# ItsyBitsy_Expander_v1_0.net
KiCad netlist of a schematic drawn in EAGLE
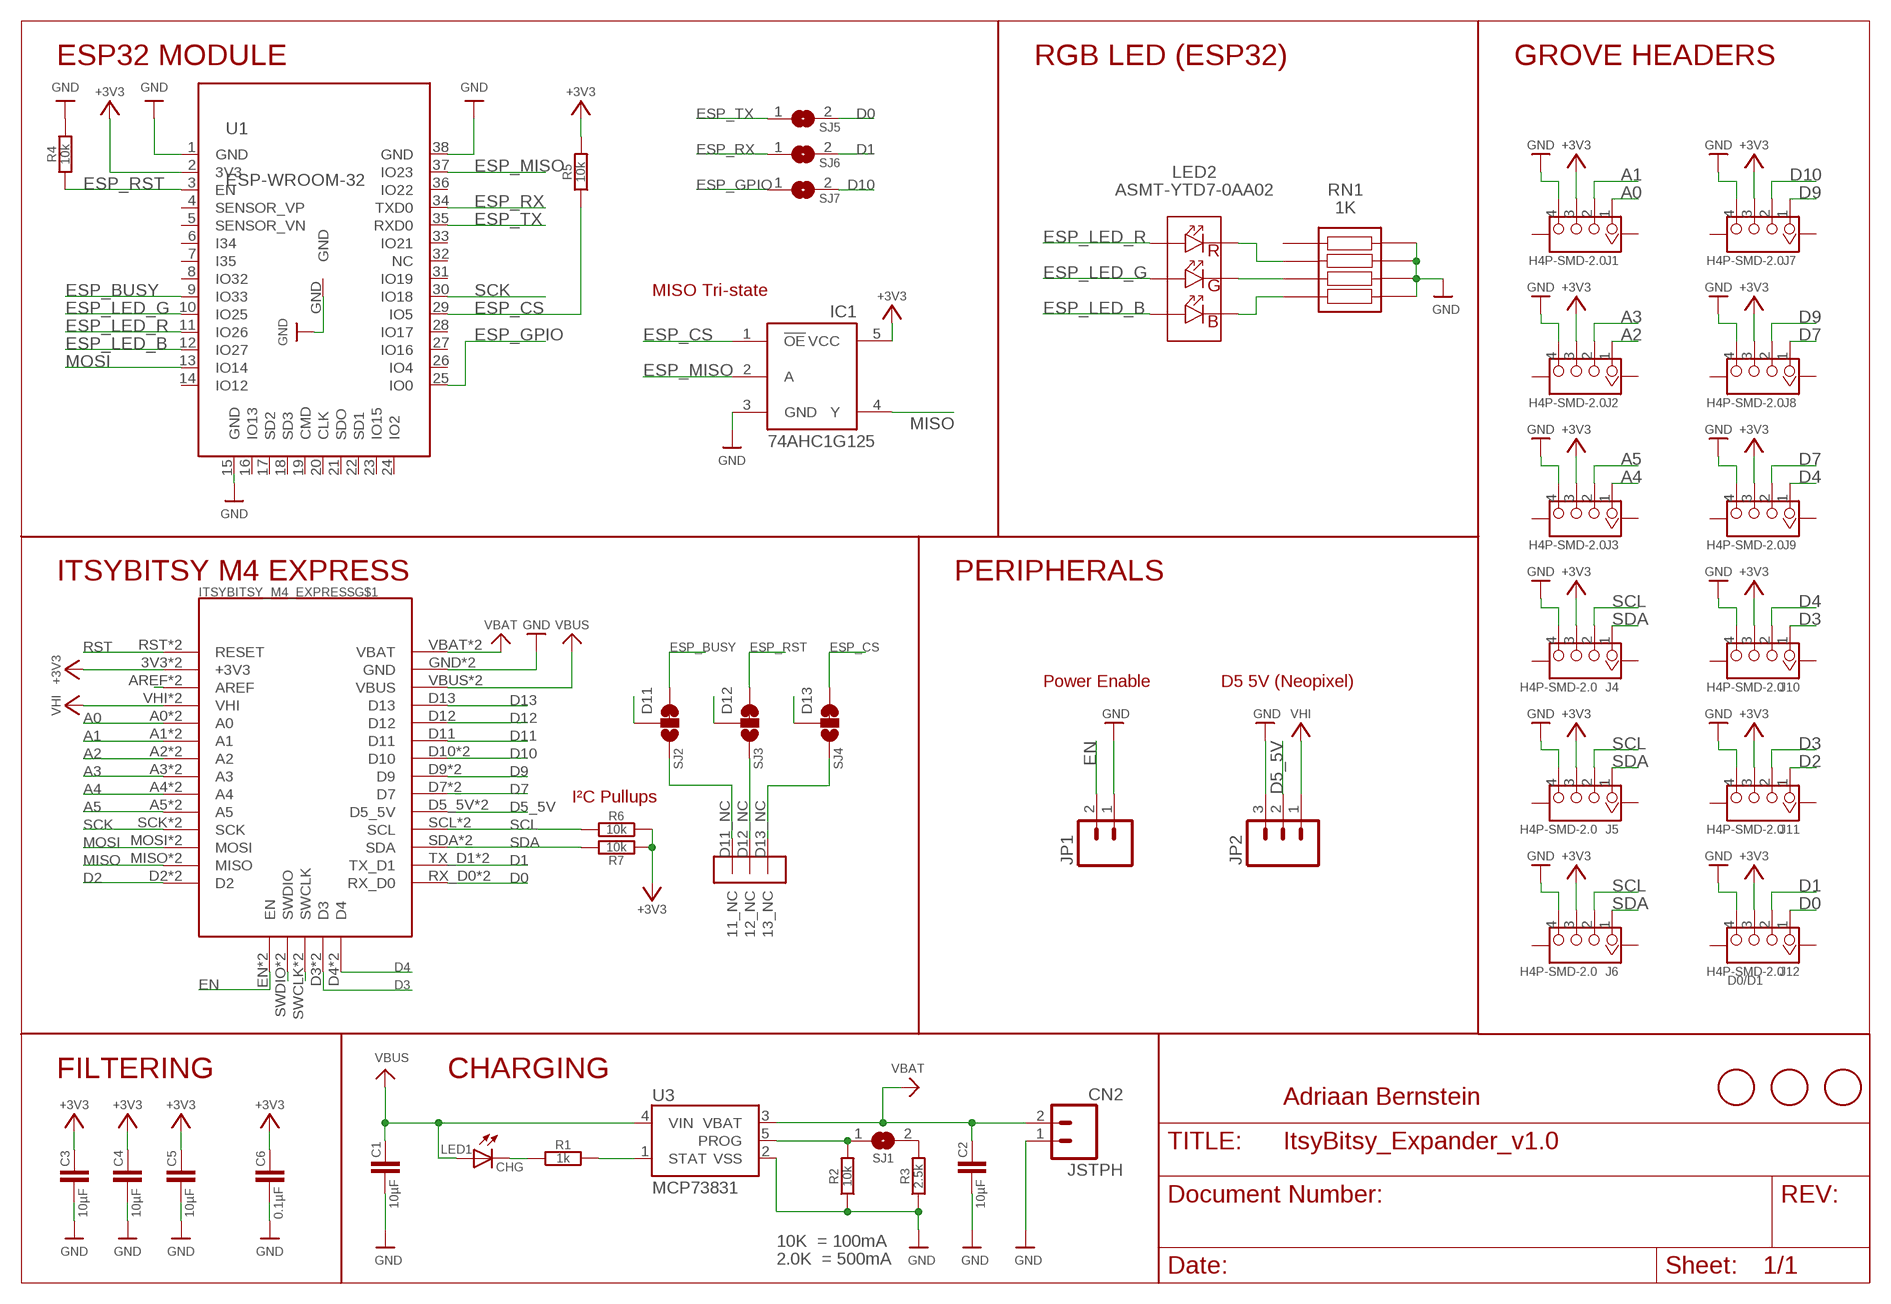
[diagram p0: schematic, sheet 1]

(export (version "E")
  (design (tool "Eeschema 10.0.6"))
  (components
    (comp (ref "C1")
      (value "10µF")
      (footprint "eagle-import:C0805")
      (libsource (lib "eagle-import") (part "C-EUC0805"))
    )
    (comp (ref "C2")
      (value "10µF")
      (footprint "eagle-import:C0805")
      (libsource (lib "eagle-import") (part "C-EUC0805"))
    )
    (comp (ref "C3")
      (value "10µF")
      (footprint "eagle-import:C0805")
      (libsource (lib "eagle-import") (part "C-EUC0805"))
    )
    (comp (ref "C4")
      (value "10µF")
      (footprint "eagle-import:C0805")
      (libsource (lib "eagle-import") (part "C-EUC0805"))
    )
    (comp (ref "C5")
      (value "10µF")
      (footprint "eagle-import:C0805")
      (libsource (lib "eagle-import") (part "C-EUC0805"))
    )
    (comp (ref "C6")
      (value "0.1µF")
      (footprint "eagle-import:C0603")
      (libsource (lib "eagle-import") (part "C-EUC0603"))
    )
    (comp (ref "CN2")
      (value "JSTPH")
      (footprint "eagle-import:JST-2-SMD")
      (libsource (lib "eagle-import") (part "M02-JST-2MM-SMT"))
    )
    (comp (ref "IC1")
      (value "74AHC1G125")
      (footprint "eagle-import:SOT23-5L")
      (libsource (lib "eagle-import") (part "74AHC1G125"))
    )
    (comp (ref "ITSYBITSY_M4_EXPRESS")
      (value "ITSYBITSY_M4_NC")
      (footprint "eagle-import:ITSYBITSY_M4_MIXED_DOUBLEHEADERS_ALL_NC")
      (libsource (lib "eagle-import") (part "ITSYBITSY_M4_NC"))
    )
    (comp (ref "J1")
      (value "H4P-SMD-2.0")
      (footprint "eagle-import:HW4-SMD-2.0")
      (libsource (lib "eagle-import") (part "GROVE-CONNECTOR-SMD(4+2P-2.0)"))
    )
    (comp (ref "J2")
      (value "H4P-SMD-2.0")
      (footprint "eagle-import:HW4-SMD-2.0")
      (libsource (lib "eagle-import") (part "GROVE-CONNECTOR-SMD(4+2P-2.0)"))
    )
    (comp (ref "J3")
      (value "H4P-SMD-2.0")
      (footprint "eagle-import:HW4-SMD-2.0")
      (libsource (lib "eagle-import") (part "GROVE-CONNECTOR-SMD(4+2P-2.0)"))
    )
    (comp (ref "J4")
      (value "H4P-SMD-2.0")
      (footprint "eagle-import:HW4-SMD-2.0")
      (libsource (lib "eagle-import") (part "GROVE-CONNECTOR-SMD(4+2P-2.0)"))
    )
    (comp (ref "J5")
      (value "H4P-SMD-2.0")
      (footprint "eagle-import:HW4-SMD-2.0")
      (libsource (lib "eagle-import") (part "GROVE-CONNECTOR-SMD(4+2P-2.0)"))
    )
    (comp (ref "J6")
      (value "H4P-SMD-2.0")
      (footprint "eagle-import:HW4-SMD-2.0")
      (libsource (lib "eagle-import") (part "GROVE-CONNECTOR-SMD(4+2P-2.0)"))
    )
    (comp (ref "J7")
      (value "H4P-SMD-2.0")
      (footprint "eagle-import:HW4-SMD-2.0")
      (libsource (lib "eagle-import") (part "GROVE-CONNECTOR-SMD(4+2P-2.0)"))
    )
    (comp (ref "J8")
      (value "H4P-SMD-2.0")
      (footprint "eagle-import:HW4-SMD-2.0")
      (libsource (lib "eagle-import") (part "GROVE-CONNECTOR-SMD(4+2P-2.0)"))
    )
    (comp (ref "J9")
      (value "H4P-SMD-2.0")
      (footprint "eagle-import:HW4-SMD-2.0")
      (libsource (lib "eagle-import") (part "GROVE-CONNECTOR-SMD(4+2P-2.0)"))
    )
    (comp (ref "J10")
      (value "H4P-SMD-2.0")
      (footprint "eagle-import:HW4-SMD-2.0")
      (libsource (lib "eagle-import") (part "GROVE-CONNECTOR-SMD(4+2P-2.0)"))
    )
    (comp (ref "J11")
      (value "H4P-SMD-2.0")
      (footprint "eagle-import:HW4-SMD-2.0")
      (libsource (lib "eagle-import") (part "GROVE-CONNECTOR-SMD(4+2P-2.0)"))
    )
    (comp (ref "J12")
      (value "H4P-SMD-2.0")
      (footprint "eagle-import:HW4-SMD-2.0")
      (libsource (lib "eagle-import") (part "GROVE-CONNECTOR-SMD(4+2P-2.0)"))
    )
    (comp (ref "JP1")
      (value "M02PTH")
      (footprint "eagle-import:1X02")
      (libsource (lib "eagle-import") (part "M02PTH"))
    )
    (comp (ref "JP2")
      (value "M03PTH")
      (footprint "eagle-import:1X03")
      (libsource (lib "eagle-import") (part "M03PTH"))
    )
    (comp (ref "LED1")
      (value "CHG")
      (footprint "eagle-import:CHIP-LED0603")
      (libsource (lib "eagle-import") (part "LEDCHIP-LED0603"))
    )
    (comp (ref "LED2")
      (value "ASMT-YTD7-0AA02")
      (footprint "eagle-import:ASMTYTD70AA02")
      (fields (field (name "MOUSER_PART_NUMBER") "630-ASMT-YTD7-0AA02"))
      (libsource (lib "eagle-import") (part "ASMT-YTD7-0AA02"))
    )
    (comp (ref "R1")
      (value "1k")
      (footprint "eagle-import:R0603")
      (libsource (lib "eagle-import") (part "R-EU_R0603"))
    )
    (comp (ref "R2")
      (value "10k")
      (footprint "eagle-import:R0603")
      (libsource (lib "eagle-import") (part "R-EU_R0603"))
    )
    (comp (ref "R3")
      (value "2.5k")
      (footprint "eagle-import:R0603")
      (libsource (lib "eagle-import") (part "R-EU_R0603"))
    )
    (comp (ref "R4")
      (value "10k")
      (footprint "eagle-import:R0603")
      (libsource (lib "eagle-import") (part "R-EU_R0603"))
    )
    (comp (ref "R5")
      (value "10k")
      (footprint "eagle-import:R0603")
      (libsource (lib "eagle-import") (part "R-EU_R0603"))
    )
    (comp (ref "R6")
      (value "10k")
      (footprint "eagle-import:R0603")
      (libsource (lib "eagle-import") (part "R-EU_R0603"))
    )
    (comp (ref "R7")
      (value "10k")
      (footprint "eagle-import:R0603")
      (libsource (lib "eagle-import") (part "R-EU_R0603"))
    )
    (comp (ref "RN1")
      (value "1K")
      (footprint "eagle-import:CAY1647R0F4LF")
      (fields
        (field (name "MANUFACTURER_PART_NUMBER") "CAY16-221J4AS")
        (field (name "MOUSER_PART_NUMBER") "652-CAY16-221J4AS")
      )
      (libsource (lib "eagle-import") (part "CAY16-221J4AS"))
    )
    (comp (ref "SJ1") (value "SJ") (footprint "eagle-import:SJ") (libsource (lib "eagle-import") (part "SJ")))
    (comp (ref "SJ5") (value "SJ") (footprint "eagle-import:SJ") (libsource (lib "eagle-import") (part "SJ")))
    (comp (ref "SJ6") (value "SJ") (footprint "eagle-import:SJ") (libsource (lib "eagle-import") (part "SJ")))
    (comp (ref "SJ7") (value "SJ") (footprint "eagle-import:SJ") (libsource (lib "eagle-import") (part "SJ")))
    (comp (ref "SJ_D11")
      (value "SJ2")
      (footprint "eagle-import:SJ_2WAY_CLOSED")
      (libsource (lib "eagle-import") (part "SJ_2WAY_CLOSED"))
    )
    (comp (ref "SJ_D12")
      (value "SJ3")
      (footprint "eagle-import:SJ_2WAY_CLOSED")
      (libsource (lib "eagle-import") (part "SJ_2WAY_CLOSED"))
    )
    (comp (ref "SJ_D13")
      (value "SJ4")
      (footprint "eagle-import:SJ_2WAY_CLOSED")
      (libsource (lib "eagle-import") (part "SJ_2WAY_CLOSED"))
    )
    (comp (ref "U$23")
      (value "FIDUCIAL")
      (footprint "eagle-import:FIDUCIAL_1MM")
      (libsource (lib "eagle-import") (part "FIDUCIAL"))
    )
    (comp (ref "U$35")
      (value "FIDUCIAL")
      (footprint "eagle-import:FIDUCIAL_1MM")
      (libsource (lib "eagle-import") (part "FIDUCIAL"))
    )
    (comp (ref "U$36")
      (value "FIDUCIAL")
      (footprint "eagle-import:FIDUCIAL_1MM")
      (libsource (lib "eagle-import") (part "FIDUCIAL"))
    )
    (comp (ref "U1")
      (value "ESP-WROOM-32")
      (footprint "eagle-import:ESP-WROOM-32")
      (libsource (lib "eagle-import") (part "ESP-WROOM-32"))
    )
    (comp (ref "U3")
      (value "MCP73831")
      (footprint "eagle-import:SOT23-5")
      (libsource (lib "eagle-import") (part "MCP73831"))
    )
  )
  (nets
    (net (code "1") (name "+3V3") (class "Default")
      (node (ref "C3") (pin "1") (pinfunction "1_1") (pintype "passive"))
      (node (ref "C4") (pin "1") (pinfunction "1_1") (pintype "passive"))
      (node (ref "C5") (pin "1") (pinfunction "1_1") (pintype "passive"))
      (node (ref "C6") (pin "1") (pinfunction "1_1") (pintype "passive"))
      (node (ref "IC1") (pin "5") (pinfunction "VCC_5") (pintype "power_in"))
      (node (ref "ITSYBITSY_M4_EXPRESS") (pin "3V3") (pinfunction "+3V3_3V3") (pintype "bidirectional"))
      (node (ref "ITSYBITSY_M4_EXPRESS") (pin "3V3_2") (pinfunction "+3V3_3V3_2") (pintype "bidirectional"))
      (node (ref "J1") (pin "3") (pinfunction "3_3") (pintype "bidirectional"))
      (node (ref "J10") (pin "3") (pinfunction "3_3") (pintype "bidirectional"))
      (node (ref "J11") (pin "3") (pinfunction "3_3") (pintype "bidirectional"))
      (node (ref "J12") (pin "3") (pinfunction "3_3") (pintype "bidirectional"))
      (node (ref "J2") (pin "3") (pinfunction "3_3") (pintype "bidirectional"))
      (node (ref "J3") (pin "3") (pinfunction "3_3") (pintype "bidirectional"))
      (node (ref "J4") (pin "3") (pinfunction "3_3") (pintype "bidirectional"))
      (node (ref "J5") (pin "3") (pinfunction "3_3") (pintype "bidirectional"))
      (node (ref "J6") (pin "3") (pinfunction "3_3") (pintype "bidirectional"))
      (node (ref "J7") (pin "3") (pinfunction "3_3") (pintype "bidirectional"))
      (node (ref "J8") (pin "3") (pinfunction "3_3") (pintype "bidirectional"))
      (node (ref "J9") (pin "3") (pinfunction "3_3") (pintype "bidirectional"))
      (node (ref "R5") (pin "2") (pinfunction "2_2") (pintype "passive"))
      (node (ref "R6") (pin "1") (pinfunction "1_1") (pintype "passive"))
      (node (ref "R7") (pin "1") (pinfunction "1_1") (pintype "passive"))
      (node (ref "U1") (pin "2") (pinfunction "3V3_2") (pintype "bidirectional"))
    )
    (net (code "2") (name "/A0") (class "Default")
      (node (ref "ITSYBITSY_M4_EXPRESS") (pin "A0") (pinfunction "A0_A0") (pintype "bidirectional"))
      (node (ref "ITSYBITSY_M4_EXPRESS") (pin "A0_2") (pinfunction "A0_A0_2") (pintype "bidirectional"))
      (node (ref "J1") (pin "1") (pinfunction "1_1") (pintype "bidirectional"))
    )
    (net (code "3") (name "/A1") (class "Default")
      (node (ref "ITSYBITSY_M4_EXPRESS") (pin "A1") (pinfunction "A1_A1") (pintype "bidirectional"))
      (node (ref "ITSYBITSY_M4_EXPRESS") (pin "A1_2") (pinfunction "A1_A1_2") (pintype "bidirectional"))
      (node (ref "J1") (pin "2") (pinfunction "2_2") (pintype "bidirectional"))
    )
    (net (code "4") (name "/A2") (class "Default")
      (node (ref "ITSYBITSY_M4_EXPRESS") (pin "A2") (pinfunction "A2_A2") (pintype "bidirectional"))
      (node (ref "ITSYBITSY_M4_EXPRESS") (pin "A2_2") (pinfunction "A2_A2_2") (pintype "bidirectional"))
      (node (ref "J2") (pin "1") (pinfunction "1_1") (pintype "bidirectional"))
    )
    (net (code "5") (name "/A3") (class "Default")
      (node (ref "ITSYBITSY_M4_EXPRESS") (pin "A3") (pinfunction "A3_A3") (pintype "bidirectional"))
      (node (ref "ITSYBITSY_M4_EXPRESS") (pin "A3_3") (pinfunction "A3_A3_3") (pintype "bidirectional"))
      (node (ref "J2") (pin "2") (pinfunction "2_2") (pintype "bidirectional"))
    )
    (net (code "6") (name "/A4") (class "Default")
      (node (ref "ITSYBITSY_M4_EXPRESS") (pin "A4") (pinfunction "A4_A4") (pintype "bidirectional"))
      (node (ref "ITSYBITSY_M4_EXPRESS") (pin "A4_2") (pinfunction "A4_A4_2") (pintype "bidirectional"))
      (node (ref "J3") (pin "1") (pinfunction "1_1") (pintype "bidirectional"))
    )
    (net (code "7") (name "/A5") (class "Default")
      (node (ref "ITSYBITSY_M4_EXPRESS") (pin "A5") (pinfunction "A5_A5") (pintype "bidirectional"))
      (node (ref "ITSYBITSY_M4_EXPRESS") (pin "A5_2") (pinfunction "A5_A5_2") (pintype "bidirectional"))
      (node (ref "J3") (pin "2") (pinfunction "2_2") (pintype "bidirectional"))
    )
    (net (code "8") (name "/D0") (class "Default")
      (node (ref "ITSYBITSY_M4_EXPRESS") (pin "RX_D0") (pinfunction "RX_D0_RX_D0") (pintype "bidirectional"))
      (node (ref "ITSYBITSY_M4_EXPRESS") (pin "RX_D0_2") (pinfunction "RX_D0_RX_D0_2") (pintype "bidirectional"))
      (node (ref "J12") (pin "1") (pinfunction "1_1") (pintype "bidirectional"))
      (node (ref "SJ5") (pin "2") (pinfunction "2_2") (pintype "passive"))
    )
    (net (code "9") (name "/D1") (class "Default")
      (node (ref "ITSYBITSY_M4_EXPRESS") (pin "TX_D1") (pinfunction "TX_D1_TX_D1") (pintype "bidirectional"))
      (node (ref "ITSYBITSY_M4_EXPRESS") (pin "TX_D1_2") (pinfunction "TX_D1_TX_D1_2") (pintype "bidirectional"))
      (node (ref "J12") (pin "2") (pinfunction "2_2") (pintype "bidirectional"))
      (node (ref "SJ6") (pin "2") (pinfunction "2_2") (pintype "passive"))
    )
    (net (code "10") (name "/D2") (class "Default")
      (node (ref "ITSYBITSY_M4_EXPRESS") (pin "D2") (pinfunction "D2_D2") (pintype "bidirectional"))
      (node (ref "ITSYBITSY_M4_EXPRESS") (pin "D2_2") (pinfunction "D2_D2_2") (pintype "bidirectional"))
      (node (ref "J11") (pin "1") (pinfunction "1_1") (pintype "bidirectional"))
    )
    (net (code "11") (name "/D3") (class "Default")
      (node (ref "ITSYBITSY_M4_EXPRESS") (pin "D3") (pinfunction "D3_D3") (pintype "bidirectional"))
      (node (ref "ITSYBITSY_M4_EXPRESS") (pin "D3_2") (pinfunction "D3_D3_2") (pintype "bidirectional"))
      (node (ref "J10") (pin "1") (pinfunction "1_1") (pintype "bidirectional"))
      (node (ref "J11") (pin "2") (pinfunction "2_2") (pintype "bidirectional"))
    )
    (net (code "12") (name "/D4") (class "Default")
      (node (ref "ITSYBITSY_M4_EXPRESS") (pin "D4") (pinfunction "D4_D4") (pintype "bidirectional"))
      (node (ref "ITSYBITSY_M4_EXPRESS") (pin "D4_2") (pinfunction "D4_D4_2") (pintype "bidirectional"))
      (node (ref "J10") (pin "2") (pinfunction "2_2") (pintype "bidirectional"))
      (node (ref "J9") (pin "1") (pinfunction "1_1") (pintype "bidirectional"))
    )
    (net (code "13") (name "/D5_5V") (class "Default")
      (node (ref "ITSYBITSY_M4_EXPRESS") (pin "D5_5V") (pinfunction "D5_5V_D5_5V") (pintype "bidirectional"))
      (node (ref "ITSYBITSY_M4_EXPRESS") (pin "D5_5V_2") (pinfunction "D5_5V_D5_5V_2") (pintype "bidirectional"))
      (node (ref "JP2") (pin "2") (pinfunction "2_2") (pintype "passive"))
    )
    (net (code "14") (name "/D7") (class "Default")
      (node (ref "ITSYBITSY_M4_EXPRESS") (pin "D7") (pinfunction "D7_D7") (pintype "bidirectional"))
      (node (ref "ITSYBITSY_M4_EXPRESS") (pin "D7_2") (pinfunction "D7_D7_2") (pintype "bidirectional"))
      (node (ref "J8") (pin "1") (pinfunction "1_1") (pintype "bidirectional"))
      (node (ref "J9") (pin "2") (pinfunction "2_2") (pintype "bidirectional"))
    )
    (net (code "15") (name "/D9") (class "Default")
      (node (ref "ITSYBITSY_M4_EXPRESS") (pin "D9") (pinfunction "D9_D9") (pintype "bidirectional"))
      (node (ref "ITSYBITSY_M4_EXPRESS") (pin "D9_2") (pinfunction "D9_D9_2") (pintype "bidirectional"))
      (node (ref "J7") (pin "1") (pinfunction "1_1") (pintype "bidirectional"))
      (node (ref "J8") (pin "2") (pinfunction "2_2") (pintype "bidirectional"))
    )
    (net (code "16") (name "/D10") (class "Default")
      (node (ref "ITSYBITSY_M4_EXPRESS") (pin "D10") (pinfunction "D10_D10") (pintype "bidirectional"))
      (node (ref "ITSYBITSY_M4_EXPRESS") (pin "D10_2") (pinfunction "D10_D10_2") (pintype "bidirectional"))
      (node (ref "J7") (pin "2") (pinfunction "2_2") (pintype "bidirectional"))
      (node (ref "SJ7") (pin "2") (pinfunction "2_2") (pintype "passive"))
    )
    (net (code "17") (name "/D11") (class "Default")
      (node (ref "ITSYBITSY_M4_EXPRESS") (pin "D11") (pinfunction "D11_D11") (pintype "bidirectional"))
      (node (ref "SJ_D11") (pin "2") (pinfunction "2_2") (pintype "passive"))
    )
    (net (code "18") (name "/D12") (class "Default")
      (node (ref "ITSYBITSY_M4_EXPRESS") (pin "D12") (pinfunction "D12_D12") (pintype "bidirectional"))
      (node (ref "SJ_D12") (pin "2") (pinfunction "2_2") (pintype "passive"))
    )
    (net (code "19") (name "/D13") (class "Default")
      (node (ref "ITSYBITSY_M4_EXPRESS") (pin "D13") (pinfunction "D13_D13") (pintype "bidirectional"))
      (node (ref "SJ_D13") (pin "2") (pinfunction "2_2") (pintype "passive"))
    )
    (net (code "20") (name "/EN") (class "Default")
      (node (ref "ITSYBITSY_M4_EXPRESS") (pin "EN") (pinfunction "EN_EN") (pintype "bidirectional"))
      (node (ref "ITSYBITSY_M4_EXPRESS") (pin "EN_2") (pinfunction "EN_EN_2") (pintype "bidirectional"))
      (node (ref "JP1") (pin "2") (pinfunction "2_2") (pintype "passive"))
    )
    (net (code "21") (name "/ESP_BUSY") (class "Default")
      (node (ref "SJ_D11") (pin "1") (pinfunction "1_1") (pintype "passive"))
      (node (ref "U1") (pin "9") (pinfunction "IO33_9") (pintype "bidirectional"))
    )
    (net (code "22") (name "/ESP_CS") (class "Default")
      (node (ref "IC1") (pin "1") (pinfunction "~{OE}_1") (pintype "input"))
      (node (ref "R5") (pin "1") (pinfunction "1_1") (pintype "passive"))
      (node (ref "SJ_D13") (pin "1") (pinfunction "1_1") (pintype "passive"))
      (node (ref "U1") (pin "29") (pinfunction "IO5_29") (pintype "bidirectional"))
    )
    (net (code "23") (name "/ESP_GPIO") (class "Default")
      (node (ref "SJ7") (pin "1") (pinfunction "1_1") (pintype "passive"))
      (node (ref "U1") (pin "25") (pinfunction "IO0_25") (pintype "bidirectional"))
    )
    (net (code "24") (name "/ESP_LED_B") (class "Default")
      (node (ref "LED2") (pin "6") (pinfunction "A_BLUE_6") (pintype "bidirectional"))
      (node (ref "U1") (pin "12") (pinfunction "IO27_12") (pintype "bidirectional"))
    )
    (net (code "25") (name "/ESP_LED_G") (class "Default")
      (node (ref "LED2") (pin "5") (pinfunction "A_GREEN_5") (pintype "bidirectional"))
      (node (ref "U1") (pin "10") (pinfunction "IO25_10") (pintype "bidirectional"))
    )
    (net (code "26") (name "/ESP_LED_R") (class "Default")
      (node (ref "LED2") (pin "4") (pinfunction "A_RED_4") (pintype "bidirectional"))
      (node (ref "U1") (pin "11") (pinfunction "IO26_11") (pintype "bidirectional"))
    )
    (net (code "27") (name "/ESP_MISO") (class "Default")
      (node (ref "IC1") (pin "2") (pinfunction "A_2") (pintype "input"))
      (node (ref "U1") (pin "37") (pinfunction "IO23_37") (pintype "bidirectional"))
    )
    (net (code "28") (name "/ESP_RST") (class "Default")
      (node (ref "R4") (pin "1") (pinfunction "1_1") (pintype "passive"))
      (node (ref "SJ_D12") (pin "1") (pinfunction "1_1") (pintype "passive"))
      (node (ref "U1") (pin "3") (pinfunction "EN_3") (pintype "bidirectional"))
    )
    (net (code "29") (name "/ESP_RX") (class "Default")
      (node (ref "SJ6") (pin "1") (pinfunction "1_1") (pintype "passive"))
      (node (ref "U1") (pin "34") (pinfunction "TXD0_34") (pintype "bidirectional"))
    )
    (net (code "30") (name "/ESP_TX") (class "Default")
      (node (ref "SJ5") (pin "1") (pinfunction "1_1") (pintype "passive"))
      (node (ref "U1") (pin "35") (pinfunction "RXD0_35") (pintype "bidirectional"))
    )
    (net (code "31") (name "/MISO") (class "Default")
      (node (ref "IC1") (pin "4") (pinfunction "Y_4") (pintype "output"))
      (node (ref "ITSYBITSY_M4_EXPRESS") (pin "MISO") (pinfunction "MISO_MISO") (pintype "bidirectional"))
      (node (ref "ITSYBITSY_M4_EXPRESS") (pin "MISO_2") (pinfunction "MISO_MISO_2") (pintype "bidirectional"))
    )
    (net (code "32") (name "/MOSI") (class "Default")
      (node (ref "ITSYBITSY_M4_EXPRESS") (pin "MOSI") (pinfunction "MOSI_MOSI") (pintype "bidirectional"))
      (node (ref "ITSYBITSY_M4_EXPRESS") (pin "MOSI_2") (pinfunction "MOSI_MOSI_2") (pintype "bidirectional"))
      (node (ref "U1") (pin "13") (pinfunction "IO14_13") (pintype "bidirectional"))
    )
    (net (code "33") (name "/RST") (class "Default")
      (node (ref "ITSYBITSY_M4_EXPRESS") (pin "RST") (pinfunction "RESET_RST") (pintype "bidirectional"))
      (node (ref "ITSYBITSY_M4_EXPRESS") (pin "RST_2") (pinfunction "RESET_RST_2") (pintype "bidirectional"))
    )
    (net (code "34") (name "/SCK") (class "Default")
      (node (ref "ITSYBITSY_M4_EXPRESS") (pin "SCK") (pinfunction "SCK_SCK") (pintype "bidirectional"))
      (node (ref "ITSYBITSY_M4_EXPRESS") (pin "SCK_2") (pinfunction "SCK_SCK_2") (pintype "bidirectional"))
      (node (ref "U1") (pin "30") (pinfunction "IO18_30") (pintype "bidirectional"))
    )
    (net (code "35") (name "/SCL") (class "Default")
      (node (ref "ITSYBITSY_M4_EXPRESS") (pin "SCL") (pinfunction "SCL_SCL") (pintype "bidirectional"))
      (node (ref "ITSYBITSY_M4_EXPRESS") (pin "SCL_2") (pinfunction "SCL_SCL_2") (pintype "bidirectional"))
      (node (ref "J4") (pin "2") (pinfunction "2_2") (pintype "bidirectional"))
      (node (ref "J5") (pin "2") (pinfunction "2_2") (pintype "bidirectional"))
      (node (ref "J6") (pin "2") (pinfunction "2_2") (pintype "bidirectional"))
      (node (ref "R6") (pin "2") (pinfunction "2_2") (pintype "passive"))
    )
    (net (code "36") (name "/SDA") (class "Default")
      (node (ref "ITSYBITSY_M4_EXPRESS") (pin "SDA") (pinfunction "SDA_SDA") (pintype "bidirectional"))
      (node (ref "ITSYBITSY_M4_EXPRESS") (pin "SDA_2") (pinfunction "SDA_SDA_2") (pintype "bidirectional"))
      (node (ref "J4") (pin "1") (pinfunction "1_1") (pintype "bidirectional"))
      (node (ref "J5") (pin "1") (pinfunction "1_1") (pintype "bidirectional"))
      (node (ref "J6") (pin "1") (pinfunction "1_1") (pintype "bidirectional"))
      (node (ref "R7") (pin "2") (pinfunction "2_2") (pintype "passive"))
    )
    (net (code "37") (name "GND") (class "Default")
      (node (ref "C1") (pin "2") (pinfunction "2_2") (pintype "passive"))
      (node (ref "C2") (pin "2") (pinfunction "2_2") (pintype "passive"))
      (node (ref "C3") (pin "2") (pinfunction "2_2") (pintype "passive"))
      (node (ref "C4") (pin "2") (pinfunction "2_2") (pintype "passive"))
      (node (ref "C5") (pin "2") (pinfunction "2_2") (pintype "passive"))
      (node (ref "C6") (pin "2") (pinfunction "2_2") (pintype "passive"))
      (node (ref "CN2") (pin "1") (pinfunction "1_1") (pintype "passive"))
      (node (ref "IC1") (pin "3") (pinfunction "GND_3") (pintype "power_in"))
      (node (ref "ITSYBITSY_M4_EXPRESS") (pin "GND") (pinfunction "GND_GND") (pintype "bidirectional"))
      (node (ref "ITSYBITSY_M4_EXPRESS") (pin "GND_2") (pinfunction "GND_GND_2") (pintype "bidirectional"))
      (node (ref "J1") (pin "4") (pinfunction "4_4") (pintype "bidirectional"))
      (node (ref "J10") (pin "4") (pinfunction "4_4") (pintype "bidirectional"))
      (node (ref "J11") (pin "4") (pinfunction "4_4") (pintype "bidirectional"))
      (node (ref "J12") (pin "4") (pinfunction "4_4") (pintype "bidirectional"))
      (node (ref "J2") (pin "4") (pinfunction "4_4") (pintype "bidirectional"))
      (node (ref "J3") (pin "4") (pinfunction "4_4") (pintype "bidirectional"))
      (node (ref "J4") (pin "4") (pinfunction "4_4") (pintype "bidirectional"))
      (node (ref "J5") (pin "4") (pinfunction "4_4") (pintype "bidirectional"))
      (node (ref "J6") (pin "4") (pinfunction "4_4") (pintype "bidirectional"))
      (node (ref "J7") (pin "4") (pinfunction "4_4") (pintype "bidirectional"))
      (node (ref "J8") (pin "4") (pinfunction "4_4") (pintype "bidirectional"))
      (node (ref "J9") (pin "4") (pinfunction "4_4") (pintype "bidirectional"))
      (node (ref "JP1") (pin "1") (pinfunction "1_1") (pintype "passive"))
      (node (ref "JP2") (pin "3") (pinfunction "3_3") (pintype "passive"))
      (node (ref "R2") (pin "1") (pinfunction "1_1") (pintype "passive"))
      (node (ref "R3") (pin "1") (pinfunction "1_1") (pintype "passive"))
      (node (ref "R4") (pin "2") (pinfunction "2_2") (pintype "passive"))
      (node (ref "RN1") (pin "5") (pinfunction "R4_2_5") (pintype "bidirectional"))
      (node (ref "RN1") (pin "6") (pinfunction "R3_2_6") (pintype "bidirectional"))
      (node (ref "RN1") (pin "7") (pinfunction "R2_2_7") (pintype "bidirectional"))
      (node (ref "RN1") (pin "8") (pinfunction "R1_2_8") (pintype "bidirectional"))
      (node (ref "U1") (pin "1") (pinfunction "GND_1") (pintype "bidirectional"))
      (node (ref "U1") (pin "15") (pinfunction "GND_15") (pintype "bidirectional"))
      (node (ref "U1") (pin "38") (pinfunction "GND_38") (pintype "bidirectional"))
      (node (ref "U1") (pin "GND") (pinfunction "GND_GND") (pintype "bidirectional"))
      (node (ref "U3") (pin "2") (pinfunction "VSS_2") (pintype "power_in"))
    )
    (net (code "38") (name "Net-(ITSYBITSY_M4_EXPRESS-PadAREF)") (class "Default")
      (node (ref "ITSYBITSY_M4_EXPRESS") (pin "AREF") (pinfunction "AREF_AREF") (pintype "bidirectional"))
      (node (ref "ITSYBITSY_M4_EXPRESS") (pin "AREF_2") (pinfunction "AREF_AREF_2") (pintype "bidirectional"))
    )
    (net (code "39") (name "Net-(ITSYBITSY_M4_EXPRESS-PadSWCLK)") (class "Default")
      (node (ref "ITSYBITSY_M4_EXPRESS") (pin "SWCLK") (pinfunction "SWCLK_SWCLK") (pintype "bidirectional"))
      (node (ref "ITSYBITSY_M4_EXPRESS") (pin "SWCLK_2") (pinfunction "SWCLK_SWCLK_2") (pintype "bidirectional"))
    )
    (net (code "40") (name "Net-(ITSYBITSY_M4_EXPRESS-PadSWDIO)") (class "Default")
      (node (ref "ITSYBITSY_M4_EXPRESS") (pin "SWDIO") (pinfunction "SWDIO_SWDIO") (pintype "bidirectional"))
      (node (ref "ITSYBITSY_M4_EXPRESS") (pin "SWDIO_2") (pinfunction "SWDIO_SWDIO_2") (pintype "bidirectional"))
    )
    (net (code "41") (name "Net-(ITSYBITSY_M4_EXPRESSB-11_NC)") (class "Default")
      (node (ref "ITSYBITSY_M4_EXPRESS") (pin "D11_NC") (pinfunction "11_NC_D11_NC") (pintype "bidirectional"))
      (node (ref "SJ_D11") (pin "3") (pinfunction "3_3") (pintype "passive"))
    )
    (net (code "42") (name "Net-(ITSYBITSY_M4_EXPRESSB-12_NC)") (class "Default")
      (node (ref "ITSYBITSY_M4_EXPRESS") (pin "D12_NC") (pinfunction "12_NC_D12_NC") (pintype "bidirectional"))
      (node (ref "SJ_D12") (pin "3") (pinfunction "3_3") (pintype "passive"))
    )
    (net (code "43") (name "Net-(ITSYBITSY_M4_EXPRESSB-13_NC)") (class "Default")
      (node (ref "ITSYBITSY_M4_EXPRESS") (pin "D13_NC") (pinfunction "13_NC_D13_NC") (pintype "bidirectional"))
      (node (ref "SJ_D13") (pin "3") (pinfunction "3_3") (pintype "passive"))
    )
    (net (code "44") (name "Net-(LED1-PadC)") (class "Default")
      (node (ref "LED1") (pin "C") (pinfunction "C_C") (pintype "passive"))
      (node (ref "R1") (pin "1") (pinfunction "1_1") (pintype "passive"))
    )
    (net (code "45") (name "Net-(LED2-K_BLUE)") (class "Default")
      (node (ref "LED2") (pin "1") (pinfunction "K_BLUE_1") (pintype "bidirectional"))
      (node (ref "RN1") (pin "4") (pinfunction "R4_1_4") (pintype "bidirectional"))
    )
    (net (code "46") (name "Net-(LED2-K_GREEN)") (class "Default")
      (node (ref "LED2") (pin "2") (pinfunction "K_GREEN_2") (pintype "bidirectional"))
      (node (ref "RN1") (pin "3") (pinfunction "R3_1_3") (pintype "bidirectional"))
    )
    (net (code "47") (name "Net-(LED2-K_RED)") (class "Default")
      (node (ref "LED2") (pin "3") (pinfunction "K_RED_3") (pintype "bidirectional"))
      (node (ref "RN1") (pin "2") (pinfunction "R2_1_2") (pintype "bidirectional"))
    )
    (net (code "48") (name "Net-(R3-Pad2)") (class "Default")
      (node (ref "R3") (pin "2") (pinfunction "2_2") (pintype "passive"))
      (node (ref "SJ1") (pin "2") (pinfunction "2_2") (pintype "passive"))
    )
    (net (code "49") (name "Net-(U3-PROG)") (class "Default")
      (node (ref "R2") (pin "2") (pinfunction "2_2") (pintype "passive"))
      (node (ref "SJ1") (pin "1") (pinfunction "1_1") (pintype "passive"))
      (node (ref "U3") (pin "5") (pinfunction "PROG_5") (pintype "input"))
    )
    (net (code "50") (name "Net-(U3-STAT)") (class "Default")
      (node (ref "R1") (pin "2") (pinfunction "2_2") (pintype "passive"))
      (node (ref "U3") (pin "1") (pinfunction "STAT_1") (pintype "output"))
    )
    (net (code "51") (name "VBAT") (class "Default")
      (node (ref "C2") (pin "1") (pinfunction "1_1") (pintype "passive"))
      (node (ref "CN2") (pin "2") (pinfunction "2_2") (pintype "passive"))
      (node (ref "ITSYBITSY_M4_EXPRESS") (pin "VBAT") (pinfunction "VBAT_VBAT") (pintype "bidirectional"))
      (node (ref "ITSYBITSY_M4_EXPRESS") (pin "VBAT_2") (pinfunction "VBAT_VBAT_2") (pintype "bidirectional"))
      (node (ref "U3") (pin "3") (pinfunction "VBAT_3") (pintype "power_in"))
    )
    (net (code "52") (name "VBUS") (class "Default")
      (node (ref "C1") (pin "1") (pinfunction "1_1") (pintype "passive"))
      (node (ref "ITSYBITSY_M4_EXPRESS") (pin "VBUS") (pinfunction "VBUS_VBUS") (pintype "bidirectional"))
      (node (ref "ITSYBITSY_M4_EXPRESS") (pin "VBUS_2") (pinfunction "VBUS_VBUS_2") (pintype "bidirectional"))
      (node (ref "LED1") (pin "A") (pinfunction "A_A") (pintype "passive"))
      (node (ref "U3") (pin "4") (pinfunction "VIN_4") (pintype "power_in"))
    )
    (net (code "53") (name "VHI") (class "Default")
      (node (ref "ITSYBITSY_M4_EXPRESS") (pin "VHI") (pinfunction "VHI_VHI") (pintype "bidirectional"))
      (node (ref "ITSYBITSY_M4_EXPRESS") (pin "VHI_2") (pinfunction "VHI_VHI_2") (pintype "bidirectional"))
      (node (ref "JP2") (pin "1") (pinfunction "1_1") (pintype "passive"))
    )
    (net (code "54") (name "unconnected-(J1-PadSS1)") (class "Default")
      (node (ref "J1") (pin "SS1") (pinfunction "SS1_SS1") (pintype "bidirectional"))
    )
    (net (code "55") (name "unconnected-(J1-PadSS2)") (class "Default")
      (node (ref "J1") (pin "SS2") (pinfunction "SS2_SS2") (pintype "bidirectional"))
    )
    (net (code "56") (name "unconnected-(J2-PadSS1)") (class "Default")
      (node (ref "J2") (pin "SS1") (pinfunction "SS1_SS1") (pintype "bidirectional"))
    )
    (net (code "57") (name "unconnected-(J2-PadSS2)") (class "Default")
      (node (ref "J2") (pin "SS2") (pinfunction "SS2_SS2") (pintype "bidirectional"))
    )
    (net (code "58") (name "unconnected-(J3-PadSS1)") (class "Default")
      (node (ref "J3") (pin "SS1") (pinfunction "SS1_SS1") (pintype "bidirectional"))
    )
    (net (code "59") (name "unconnected-(J3-PadSS2)") (class "Default")
      (node (ref "J3") (pin "SS2") (pinfunction "SS2_SS2") (pintype "bidirectional"))
    )
    (net (code "60") (name "unconnected-(J4-PadSS1)") (class "Default")
      (node (ref "J4") (pin "SS1") (pinfunction "SS1_SS1") (pintype "bidirectional"))
    )
    (net (code "61") (name "unconnected-(J4-PadSS2)") (class "Default")
      (node (ref "J4") (pin "SS2") (pinfunction "SS2_SS2") (pintype "bidirectional"))
    )
    (net (code "62") (name "unconnected-(J5-PadSS1)") (class "Default")
      (node (ref "J5") (pin "SS1") (pinfunction "SS1_SS1") (pintype "bidirectional"))
    )
    (net (code "63") (name "unconnected-(J5-PadSS2)") (class "Default")
      (node (ref "J5") (pin "SS2") (pinfunction "SS2_SS2") (pintype "bidirectional"))
    )
    (net (code "64") (name "unconnected-(J6-PadSS1)") (class "Default")
      (node (ref "J6") (pin "SS1") (pinfunction "SS1_SS1") (pintype "bidirectional"))
    )
    (net (code "65") (name "unconnected-(J6-PadSS2)") (class "Default")
      (node (ref "J6") (pin "SS2") (pinfunction "SS2_SS2") (pintype "bidirectional"))
    )
    (net (code "66") (name "unconnected-(J7-PadSS1)") (class "Default")
      (node (ref "J7") (pin "SS1") (pinfunction "SS1_SS1") (pintype "bidirectional"))
    )
    (net (code "67") (name "unconnected-(J7-PadSS2)") (class "Default")
      (node (ref "J7") (pin "SS2") (pinfunction "SS2_SS2") (pintype "bidirectional"))
    )
    (net (code "68") (name "unconnected-(J8-PadSS1)") (class "Default")
      (node (ref "J8") (pin "SS1") (pinfunction "SS1_SS1") (pintype "bidirectional"))
    )
    (net (code "69") (name "unconnected-(J8-PadSS2)") (class "Default")
      (node (ref "J8") (pin "SS2") (pinfunction "SS2_SS2") (pintype "bidirectional"))
    )
    (net (code "70") (name "unconnected-(J9-PadSS1)") (class "Default")
      (node (ref "J9") (pin "SS1") (pinfunction "SS1_SS1") (pintype "bidirectional"))
    )
    (net (code "71") (name "unconnected-(J9-PadSS2)") (class "Default")
      (node (ref "J9") (pin "SS2") (pinfunction "SS2_SS2") (pintype "bidirectional"))
    )
    (net (code "72") (name "unconnected-(J10-PadSS1)") (class "Default")
      (node (ref "J10") (pin "SS1") (pinfunction "SS1_SS1") (pintype "bidirectional"))
    )
    (net (code "73") (name "unconnected-(J10-PadSS2)") (class "Default")
      (node (ref "J10") (pin "SS2") (pinfunction "SS2_SS2") (pintype "bidirectional"))
    )
    (net (code "74") (name "unconnected-(J11-PadSS1)") (class "Default")
      (node (ref "J11") (pin "SS1") (pinfunction "SS1_SS1") (pintype "bidirectional"))
    )
    (net (code "75") (name "unconnected-(J11-PadSS2)") (class "Default")
      (node (ref "J11") (pin "SS2") (pinfunction "SS2_SS2") (pintype "bidirectional"))
    )
    (net (code "76") (name "unconnected-(J12-PadSS1)") (class "Default")
      (node (ref "J12") (pin "SS1") (pinfunction "SS1_SS1") (pintype "bidirectional"))
    )
    (net (code "77") (name "unconnected-(J12-PadSS2)") (class "Default")
      (node (ref "J12") (pin "SS2") (pinfunction "SS2_SS2") (pintype "bidirectional"))
    )
    (net (code "78") (name "unconnected-(RN1-R1_1-Pad1)") (class "Default")
      (node (ref "RN1") (pin "1") (pinfunction "R1_1_1") (pintype "bidirectional"))
    )
    (net (code "79") (name "unconnected-(U1-CLK-Pad20)") (class "Default")
      (node (ref "U1") (pin "20") (pinfunction "CLK_20") (pintype "bidirectional"))
    )
    (net (code "80") (name "unconnected-(U1-CMD-Pad19)") (class "Default")
      (node (ref "U1") (pin "19") (pinfunction "CMD_19") (pintype "bidirectional"))
    )
    (net (code "81") (name "unconnected-(U1-I34-Pad6)") (class "Default")
      (node (ref "U1") (pin "6") (pinfunction "I34_6") (pintype "input"))
    )
    (net (code "82") (name "unconnected-(U1-I35-Pad7)") (class "Default")
      (node (ref "U1") (pin "7") (pinfunction "I35_7") (pintype "input"))
    )
    (net (code "83") (name "unconnected-(U1-IO2-Pad24)") (class "Default")
      (node (ref "U1") (pin "24") (pinfunction "IO2_24") (pintype "bidirectional"))
    )
    (net (code "84") (name "unconnected-(U1-IO4-Pad26)") (class "Default")
      (node (ref "U1") (pin "26") (pinfunction "IO4_26") (pintype "bidirectional"))
    )
    (net (code "85") (name "unconnected-(U1-IO12-Pad14)") (class "Default")
      (node (ref "U1") (pin "14") (pinfunction "IO12_14") (pintype "bidirectional"))
    )
    (net (code "86") (name "unconnected-(U1-IO13-Pad16)") (class "Default")
      (node (ref "U1") (pin "16") (pinfunction "IO13_16") (pintype "bidirectional"))
    )
    (net (code "87") (name "unconnected-(U1-IO15-Pad23)") (class "Default")
      (node (ref "U1") (pin "23") (pinfunction "IO15_23") (pintype "bidirectional"))
    )
    (net (code "88") (name "unconnected-(U1-IO16-Pad27)") (class "Default")
      (node (ref "U1") (pin "27") (pinfunction "IO16_27") (pintype "bidirectional"))
    )
    (net (code "89") (name "unconnected-(U1-IO17-Pad28)") (class "Default")
      (node (ref "U1") (pin "28") (pinfunction "IO17_28") (pintype "bidirectional"))
    )
    (net (code "90") (name "unconnected-(U1-IO19-Pad31)") (class "Default")
      (node (ref "U1") (pin "31") (pinfunction "IO19_31") (pintype "bidirectional"))
    )
    (net (code "91") (name "unconnected-(U1-IO21-Pad33)") (class "Default")
      (node (ref "U1") (pin "33") (pinfunction "IO21_33") (pintype "bidirectional"))
    )
    (net (code "92") (name "unconnected-(U1-IO22-Pad36)") (class "Default")
      (node (ref "U1") (pin "36") (pinfunction "IO22_36") (pintype "bidirectional"))
    )
    (net (code "93") (name "unconnected-(U1-IO32-Pad8)") (class "Default")
      (node (ref "U1") (pin "8") (pinfunction "IO32_8") (pintype "bidirectional"))
    )
    (net (code "94") (name "unconnected-(U1-NC-Pad32)") (class "Default")
      (node (ref "U1") (pin "32") (pinfunction "NC_32") (pintype "bidirectional"))
    )
    (net (code "95") (name "unconnected-(U1-SD1-Pad22)") (class "Default")
      (node (ref "U1") (pin "22") (pinfunction "SD1_22") (pintype "bidirectional"))
    )
    (net (code "96") (name "unconnected-(U1-SD2-Pad17)") (class "Default")
      (node (ref "U1") (pin "17") (pinfunction "SD2_17") (pintype "bidirectional"))
    )
    (net (code "97") (name "unconnected-(U1-SD3-Pad18)") (class "Default")
      (node (ref "U1") (pin "18") (pinfunction "SD3_18") (pintype "bidirectional"))
    )
    (net (code "98") (name "unconnected-(U1-SDO-Pad21)") (class "Default")
      (node (ref "U1") (pin "21") (pinfunction "SDO_21") (pintype "bidirectional"))
    )
    (net (code "99") (name "unconnected-(U1-SENSOR_VN-Pad5)") (class "Default")
      (node (ref "U1") (pin "5") (pinfunction "SENSOR_VN_5") (pintype "input"))
    )
    (net (code "100") (name "unconnected-(U1-SENSOR_VP-Pad4)") (class "Default")
      (node (ref "U1") (pin "4") (pinfunction "SENSOR_VP_4") (pintype "input"))
    )
  )
)
